# RocketSenseV2.net
KiCad netlist of a schematic drawn in EAGLE
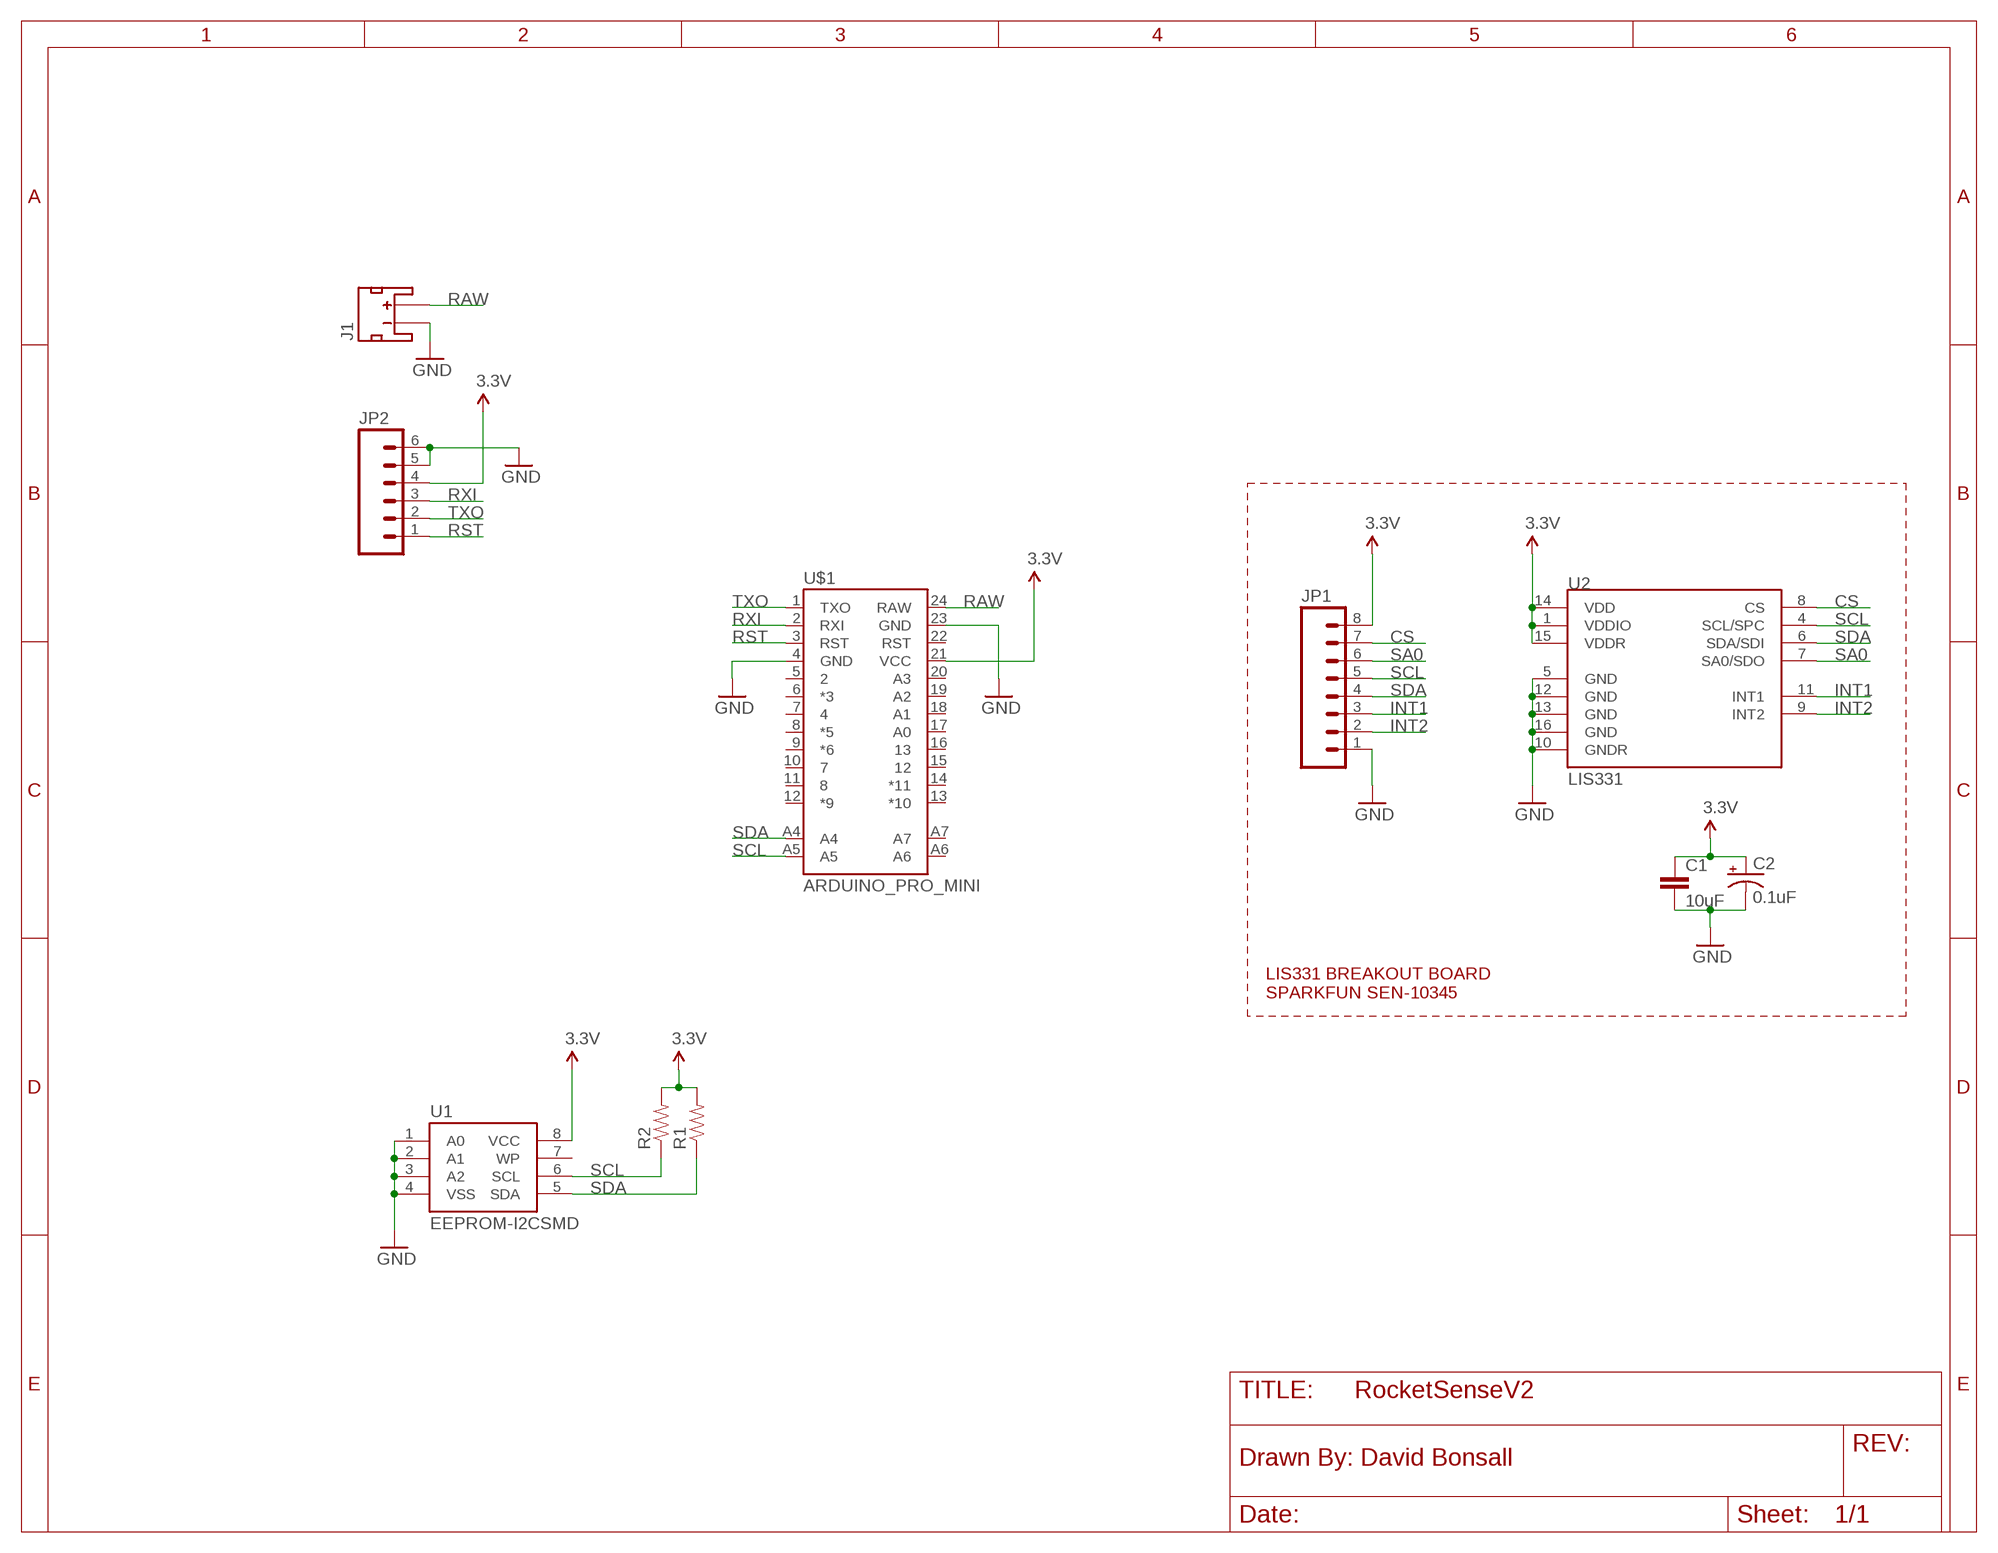
[diagram p0: schematic, sheet 1]

(export (version "E")
  (design (tool "Eeschema 10.0.6"))
  (components
    (comp (ref "C1")
      (value "10uF")
      (footprint "eagle-import:0402-CAP")
      (libsource (lib "eagle-import") (part "CAP0402-CAP"))
    )
    (comp (ref "C2")
      (value "0.1uF")
      (footprint "eagle-import:EIA3216")
      (libsource (lib "eagle-import") (part "CAP_POL1206"))
    )
    (comp (ref "J1")
      (value "JST_2MM_MALE")
      (footprint "eagle-import:JST-2-SMD")
      (libsource (lib "eagle-import") (part "JST_2MM_MALE"))
    )
    (comp (ref "JP1")
      (value "M08")
      (footprint "eagle-import:1X08_PIN1_NO_SILK")
      (libsource (lib "eagle-import") (part "M08"))
    )
    (comp (ref "JP2")
      (value "M06SIP")
      (footprint "eagle-import:1X06")
      (libsource (lib "eagle-import") (part "M06SIP"))
    )
    (comp (ref "R1")
      (value "RESISTORPTH-1/6W")
      (footprint "eagle-import:1_6W-RES")
      (libsource (lib "eagle-import") (part "RESISTORPTH-1/6W"))
    )
    (comp (ref "R2")
      (value "RESISTORPTH-1/6W")
      (footprint "eagle-import:1_6W-RES")
      (libsource (lib "eagle-import") (part "RESISTORPTH-1/6W"))
    )
    (comp (ref "U$1")
      (value "ARDUINO_PRO_MINI")
      (footprint "eagle-import:ARDUINO_PRO_MINI")
      (libsource (lib "eagle-import") (part "ARDUINO_PRO_MINI"))
    )
    (comp (ref "U1")
      (value "EEPROM-I2CSMD")
      (footprint "eagle-import:SO08")
      (libsource (lib "eagle-import") (part "EEPROM-I2CSMD"))
    )
    (comp (ref "U2")
      (value "LIS331")
      (footprint "eagle-import:LGA16-3MM")
      (libsource (lib "eagle-import") (part "LIS331"))
    )
  )
  (nets
    (net (code "1") (name "/CS") (class "Default")
      (node (ref "JP1") (pin "7") (pinfunction "7_7") (pintype "passive"))
      (node (ref "U2") (pin "8") (pinfunction "CS_8") (pintype "bidirectional"))
    )
    (net (code "2") (name "/INT1") (class "Default")
      (node (ref "JP1") (pin "3") (pinfunction "3_3") (pintype "passive"))
      (node (ref "U2") (pin "11") (pinfunction "INT1_11") (pintype "bidirectional"))
    )
    (net (code "3") (name "/INT2") (class "Default")
      (node (ref "JP1") (pin "2") (pinfunction "2_2") (pintype "passive"))
      (node (ref "U2") (pin "9") (pinfunction "INT2_9") (pintype "bidirectional"))
    )
    (net (code "4") (name "/RAW") (class "Default")
      (node (ref "J1") (pin "2") (pinfunction "+_2") (pintype "bidirectional"))
      (node (ref "U$1") (pin "24") (pinfunction "RAW_24") (pintype "bidirectional"))
    )
    (net (code "5") (name "/RST") (class "Default")
      (node (ref "JP2") (pin "1") (pinfunction "1_1") (pintype "passive"))
      (node (ref "U$1") (pin "3") (pinfunction "RST_3") (pintype "bidirectional"))
    )
    (net (code "6") (name "/RXI") (class "Default")
      (node (ref "JP2") (pin "3") (pinfunction "3_3") (pintype "passive"))
      (node (ref "U$1") (pin "2") (pinfunction "RXI_2") (pintype "bidirectional"))
    )
    (net (code "7") (name "/SA0") (class "Default")
      (node (ref "JP1") (pin "6") (pinfunction "6_6") (pintype "passive"))
      (node (ref "U2") (pin "7") (pinfunction "SA0/SDO_7") (pintype "bidirectional"))
    )
    (net (code "8") (name "/SCL") (class "Default")
      (node (ref "JP1") (pin "5") (pinfunction "5_5") (pintype "passive"))
      (node (ref "R2") (pin "1") (pinfunction "1_1") (pintype "passive"))
      (node (ref "U$1") (pin "A5") (pinfunction "A5_A5") (pintype "bidirectional"))
      (node (ref "U1") (pin "6") (pinfunction "SCL_6") (pintype "bidirectional"))
      (node (ref "U2") (pin "4") (pinfunction "SCL/SPC_4") (pintype "bidirectional"))
    )
    (net (code "9") (name "/SDA") (class "Default")
      (node (ref "JP1") (pin "4") (pinfunction "4_4") (pintype "passive"))
      (node (ref "R1") (pin "1") (pinfunction "1_1") (pintype "passive"))
      (node (ref "U$1") (pin "A4") (pinfunction "A4_A4") (pintype "bidirectional"))
      (node (ref "U1") (pin "5") (pinfunction "SDA_5") (pintype "bidirectional"))
      (node (ref "U2") (pin "6") (pinfunction "SDA/SDI_6") (pintype "bidirectional"))
    )
    (net (code "10") (name "/TXO") (class "Default")
      (node (ref "JP2") (pin "2") (pinfunction "2_2") (pintype "passive"))
      (node (ref "U$1") (pin "1") (pinfunction "TXO_1") (pintype "bidirectional"))
    )
    (net (code "11") (name "3.3V") (class "Default")
      (node (ref "C1") (pin "1") (pinfunction "1_1") (pintype "passive"))
      (node (ref "C2") (pin "A") (pinfunction "+_A") (pintype "passive"))
      (node (ref "JP1") (pin "8") (pinfunction "8_8") (pintype "passive"))
      (node (ref "JP2") (pin "4") (pinfunction "4_4") (pintype "passive"))
      (node (ref "R1") (pin "2") (pinfunction "2_2") (pintype "passive"))
      (node (ref "R2") (pin "2") (pinfunction "2_2") (pintype "passive"))
      (node (ref "U$1") (pin "21") (pinfunction "VCC_21") (pintype "bidirectional"))
      (node (ref "U1") (pin "8") (pinfunction "VCC_8") (pintype "power_in"))
      (node (ref "U2") (pin "1") (pinfunction "VDDIO_1") (pintype "bidirectional"))
      (node (ref "U2") (pin "14") (pinfunction "VDD_14") (pintype "bidirectional"))
      (node (ref "U2") (pin "15") (pinfunction "VDDR_15") (pintype "bidirectional"))
    )
    (net (code "12") (name "GND") (class "Default")
      (node (ref "C1") (pin "2") (pinfunction "2_2") (pintype "passive"))
      (node (ref "C2") (pin "C") (pinfunction "-_C") (pintype "passive"))
      (node (ref "J1") (pin "1") (pinfunction "-_1") (pintype "bidirectional"))
      (node (ref "JP1") (pin "1") (pinfunction "1_1") (pintype "passive"))
      (node (ref "JP2") (pin "5") (pinfunction "5_5") (pintype "passive"))
      (node (ref "JP2") (pin "6") (pinfunction "6_6") (pintype "passive"))
      (node (ref "U$1") (pin "23") (pinfunction "GND_23") (pintype "bidirectional"))
      (node (ref "U$1") (pin "4") (pinfunction "GND_4") (pintype "bidirectional"))
      (node (ref "U1") (pin "1") (pinfunction "A0_1") (pintype "bidirectional"))
      (node (ref "U1") (pin "2") (pinfunction "A1_2") (pintype "bidirectional"))
      (node (ref "U1") (pin "3") (pinfunction "A2_3") (pintype "bidirectional"))
      (node (ref "U1") (pin "4") (pinfunction "VSS_4") (pintype "power_in"))
      (node (ref "U2") (pin "10") (pinfunction "GNDR_10") (pintype "bidirectional"))
      (node (ref "U2") (pin "12") (pinfunction "GND_12") (pintype "bidirectional"))
      (node (ref "U2") (pin "13") (pinfunction "GND_13") (pintype "bidirectional"))
      (node (ref "U2") (pin "16") (pinfunction "GND_16") (pintype "bidirectional"))
      (node (ref "U2") (pin "5") (pinfunction "GND_5") (pintype "bidirectional"))
    )
    (net (code "13") (name "unconnected-(J1-PAD1-PadNC1)") (class "Default")
      (node (ref "J1") (pin "NC1") (pinfunction "PAD1_NC1") (pintype "bidirectional"))
    )
    (net (code "14") (name "unconnected-(J1-PAD2-PadNC2)") (class "Default")
      (node (ref "J1") (pin "NC2") (pinfunction "PAD2_NC2") (pintype "bidirectional"))
    )
    (net (code "15") (name "unconnected-(U$1-*3-Pad6)") (class "Default")
      (node (ref "U$1") (pin "6") (pinfunction "*3_6") (pintype "bidirectional"))
    )
    (net (code "16") (name "unconnected-(U$1-*5-Pad8)") (class "Default")
      (node (ref "U$1") (pin "8") (pinfunction "*5_8") (pintype "bidirectional"))
    )
    (net (code "17") (name "unconnected-(U$1-*6-Pad9)") (class "Default")
      (node (ref "U$1") (pin "9") (pinfunction "*6_9") (pintype "bidirectional"))
    )
    (net (code "18") (name "unconnected-(U$1-*9-Pad12)") (class "Default")
      (node (ref "U$1") (pin "12") (pinfunction "*9_12") (pintype "bidirectional"))
    )
    (net (code "19") (name "unconnected-(U$1-*10-Pad13)") (class "Default")
      (node (ref "U$1") (pin "13") (pinfunction "*10_13") (pintype "bidirectional"))
    )
    (net (code "20") (name "unconnected-(U$1-*11-Pad14)") (class "Default")
      (node (ref "U$1") (pin "14") (pinfunction "*11_14") (pintype "bidirectional"))
    )
    (net (code "21") (name "unconnected-(U$1-2-Pad5)") (class "Default")
      (node (ref "U$1") (pin "5") (pinfunction "2_5") (pintype "bidirectional"))
    )
    (net (code "22") (name "unconnected-(U$1-4-Pad7)") (class "Default")
      (node (ref "U$1") (pin "7") (pinfunction "4_7") (pintype "bidirectional"))
    )
    (net (code "23") (name "unconnected-(U$1-7-Pad10)") (class "Default")
      (node (ref "U$1") (pin "10") (pinfunction "7_10") (pintype "bidirectional"))
    )
    (net (code "24") (name "unconnected-(U$1-8-Pad11)") (class "Default")
      (node (ref "U$1") (pin "11") (pinfunction "8_11") (pintype "bidirectional"))
    )
    (net (code "25") (name "unconnected-(U$1-12-Pad15)") (class "Default")
      (node (ref "U$1") (pin "15") (pinfunction "12_15") (pintype "bidirectional"))
    )
    (net (code "26") (name "unconnected-(U$1-13-Pad16)") (class "Default")
      (node (ref "U$1") (pin "16") (pinfunction "13_16") (pintype "bidirectional"))
    )
    (net (code "27") (name "unconnected-(U$1-A0-Pad17)") (class "Default")
      (node (ref "U$1") (pin "17") (pinfunction "A0_17") (pintype "bidirectional"))
    )
    (net (code "28") (name "unconnected-(U$1-A1-Pad18)") (class "Default")
      (node (ref "U$1") (pin "18") (pinfunction "A1_18") (pintype "bidirectional"))
    )
    (net (code "29") (name "unconnected-(U$1-A2-Pad19)") (class "Default")
      (node (ref "U$1") (pin "19") (pinfunction "A2_19") (pintype "bidirectional"))
    )
    (net (code "30") (name "unconnected-(U$1-A3-Pad20)") (class "Default")
      (node (ref "U$1") (pin "20") (pinfunction "A3_20") (pintype "bidirectional"))
    )
    (net (code "31") (name "unconnected-(U$1-PadA6)") (class "Default")
      (node (ref "U$1") (pin "A6") (pinfunction "A6_A6") (pintype "bidirectional"))
    )
    (net (code "32") (name "unconnected-(U$1-PadA7)") (class "Default")
      (node (ref "U$1") (pin "A7") (pinfunction "A7_A7") (pintype "bidirectional"))
    )
    (net (code "33") (name "unconnected-(U$1-RST-Pad22)") (class "Default")
      (node (ref "U$1") (pin "22") (pinfunction "RST_22") (pintype "bidirectional"))
    )
    (net (code "34") (name "unconnected-(U1-WP-Pad7)") (class "Default")
      (node (ref "U1") (pin "7") (pinfunction "WP_7") (pintype "bidirectional"))
    )
  )
)
